# Power_Distribution_-_External_ADC.net
KiCad netlist of a schematic drawn in Altium Designer
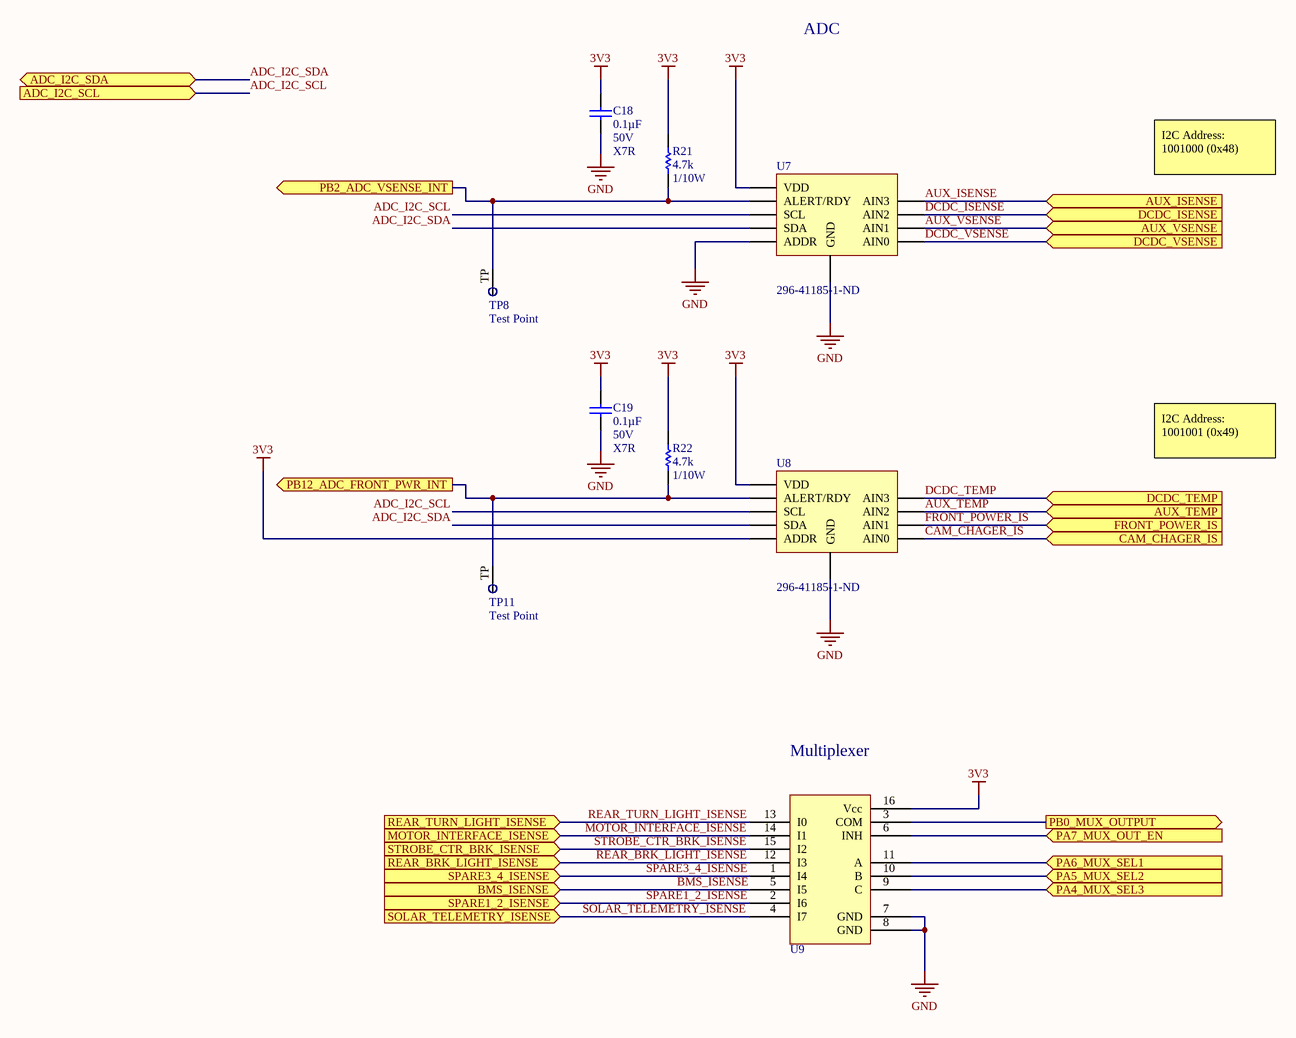
[diagram p0: Power Distribution - External ADC.SchDoc]

(export (version "E")
  (design (tool "Eeschema 10.0.6"))
  (components
    (comp (ref "C18")
      (value "CAP CER 0.1UF 50V 10% X7R 0603")
      (footprint "CAP, 0603")
      (description "0.10µF ±10% 50V Ceramic Capacitor X7R 0603 (1608 Metric)")
      (fields
        (field (name "TOLERANCE") "±10%")
        (field (name "CAPACITANCE") "0.1µF")
        (field (name "VOLTAGE") "50V")
        (field (name "TEMPERATURE COEFFICIENT") "X7R")
      )
      (libsource (lib "Schematic Diagrams") (part "CAP CER 0.1UF 50V 10% X7R 0603"))
    )
    (comp (ref "C19")
      (value "CAP CER 0.1UF 50V 10% X7R 0603")
      (footprint "CAP, 0603")
      (description "0.10µF ±10% 50V Ceramic Capacitor X7R 0603 (1608 Metric)")
      (fields
        (field (name "TOLERANCE") "±10%")
        (field (name "CAPACITANCE") "0.1µF")
        (field (name "VOLTAGE") "50V")
        (field (name "TEMPERATURE COEFFICIENT") "X7R")
      )
      (libsource (lib "Schematic Diagrams") (part "CAP CER 0.1UF 50V 10% X7R 0603"))
    )
    (comp (ref "R21")
      (value "RES 4.7K OHM 1% 1/10W 0603")
      (footprint "RES, 0603")
      (description "4.7k Ohm ±1% 0.1W, 1/10W Chip Resistor 0603 (1608 Metric) Moisture Resistant Thick Film")
      (fields
        (field (name "TOLERANCE") "±1%")
        (field (name "RESISTANCE (OHMS)") "4.7k")
        (field (name "POWER (WATTS)") "1/10W")
      )
      (libsource (lib "Schematic Diagrams") (part "RES 4.7K OHM 1% 1/10W 0603"))
    )
    (comp (ref "R22")
      (value "RES 4.7K OHM 1% 1/10W 0603")
      (footprint "RES, 0603")
      (description "4.7k Ohm ±1% 0.1W, 1/10W Chip Resistor 0603 (1608 Metric) Moisture Resistant Thick Film")
      (fields
        (field (name "TOLERANCE") "±1%")
        (field (name "RESISTANCE (OHMS)") "4.7k")
        (field (name "POWER (WATTS)") "1/10W")
      )
      (libsource (lib "Schematic Diagrams") (part "RES 4.7K OHM 1% 1/10W 0603"))
    )
    (comp (ref "TP8")
      (value "Test Point")
      (footprint "Test Point")
      (libsource (lib "Schematic Diagrams") (part "Test Point"))
    )
    (comp (ref "TP11")
      (value "Test Point")
      (footprint "Test Point")
      (libsource (lib "Schematic Diagrams") (part "Test Point"))
    )
    (comp (ref "U7")
      (value "Quad ADC")
      (footprint "IC ADC VSSOP10")
      (description "12 Bit Analog to Digital Converter 4 Input 1 Sigma-Delta 10-VSSOP")
      (fields
        (field (name "MANUFACTURER") "Texas Instruments")
        (field (name "MANUFACTURER PART NUMBER") "ADS1015IDGSR")
        (field (name "SUPPLIER PART NUMBER 1") "296-41185-1-ND")
      )
      (libsource (lib "Schematic Diagrams") (part "IC ADC 12-BIT VSSOP-10"))
    )
    (comp (ref "U8")
      (value "Quad ADC")
      (footprint "IC ADC VSSOP10")
      (description "12 Bit Analog to Digital Converter 4 Input 1 Sigma-Delta 10-VSSOP")
      (fields
        (field (name "MANUFACTURER") "Texas Instruments")
        (field (name "MANUFACTURER PART NUMBER") "ADS1015IDGSR")
        (field (name "SUPPLIER PART NUMBER 1") "296-41185-1-ND")
      )
      (libsource (lib "Schematic Diagrams") (part "IC ADC 12-BIT VSSOP-10"))
    )
    (comp (ref "U9")
      (value "IC MUX/DMUX 8X1 16TSSOP")
      (footprint "16-TSSOP")
      (description "1 Circuit IC Switch 8:1 75Ohm 16-TSSOP")
      (fields (field (name "MANUFACTURER") "Texas Instruments"))
      (libsource (lib "Schematic Diagrams") (part "IC MUX/DMUX 8X1 16TSSOP"))
    )
  )
  (nets
    (net (code "1") (name "/ADC_I2C_SCL") (class "Default")
      (node (ref "U7") (pin "10") (pinfunction "SCL_10") (pintype "passive"))
      (node (ref "U8") (pin "10") (pinfunction "SCL_10") (pintype "passive"))
    )
    (net (code "2") (name "/ADC_I2C_SDA") (class "Default")
      (node (ref "U7") (pin "9") (pinfunction "SDA_9") (pintype "passive"))
      (node (ref "U8") (pin "9") (pinfunction "SDA_9") (pintype "passive"))
    )
    (net (code "3") (name "/AUX_ISENSE") (class "Default")
      (node (ref "U7") (pin "7") (pinfunction "AIN3_7") (pintype "passive"))
    )
    (net (code "4") (name "/AUX_TEMP") (class "Default")
      (node (ref "U8") (pin "6") (pinfunction "AIN2_6") (pintype "passive"))
    )
    (net (code "5") (name "/AUX_VSENSE") (class "Default")
      (node (ref "U7") (pin "5") (pinfunction "AIN1_5") (pintype "passive"))
    )
    (net (code "6") (name "/BMS_ISENSE") (class "Default")
      (node (ref "U9") (pin "5") (pinfunction "I5_5") (pintype "passive"))
    )
    (net (code "7") (name "/CAM_CHAGER_IS") (class "Default")
      (node (ref "U8") (pin "4") (pinfunction "AIN0_4") (pintype "passive"))
    )
    (net (code "8") (name "/DCDC_ISENSE") (class "Default")
      (node (ref "U7") (pin "6") (pinfunction "AIN2_6") (pintype "passive"))
    )
    (net (code "9") (name "/DCDC_TEMP") (class "Default")
      (node (ref "U8") (pin "7") (pinfunction "AIN3_7") (pintype "passive"))
    )
    (net (code "10") (name "/DCDC_VSENSE") (class "Default")
      (node (ref "U7") (pin "4") (pinfunction "AIN0_4") (pintype "passive"))
    )
    (net (code "11") (name "/FRONT_POWER_IS") (class "Default")
      (node (ref "U8") (pin "5") (pinfunction "AIN1_5") (pintype "passive"))
    )
    (net (code "12") (name "/MOTOR_INTERFACE_ISENSE") (class "Default")
      (node (ref "U9") (pin "14") (pinfunction "I1_14") (pintype "passive"))
    )
    (net (code "13") (name "/PA4_MUX_SEL3") (class "Default")
      (node (ref "U9") (pin "9") (pinfunction "C_9") (pintype "passive"))
    )
    (net (code "14") (name "/PA5_MUX_SEL2") (class "Default")
      (node (ref "U9") (pin "10") (pinfunction "B_10") (pintype "passive"))
    )
    (net (code "15") (name "/PA6_MUX_SEL1") (class "Default")
      (node (ref "U9") (pin "11") (pinfunction "A_11") (pintype "passive"))
    )
    (net (code "16") (name "/PA7_MUX_OUT_EN") (class "Default")
      (node (ref "U9") (pin "6") (pinfunction "INH_6") (pintype "passive"))
    )
    (net (code "17") (name "/PB0_MUX_OUTPUT") (class "Default")
      (node (ref "U9") (pin "3") (pinfunction "COM_3") (pintype "passive"))
    )
    (net (code "18") (name "/PB2_ADC_VSENSE_INT") (class "Default")
      (node (ref "R21") (pin "2") (pinfunction "2_2") (pintype "passive"))
      (node (ref "TP8") (pin "TP") (pinfunction "1_TP") (pintype "passive"))
      (node (ref "U7") (pin "2") (pinfunction "ALERT/RDY_2") (pintype "passive"))
    )
    (net (code "19") (name "/PB12_ADC_FRONT_PWR_INT") (class "Default")
      (node (ref "R22") (pin "2") (pinfunction "2_2") (pintype "passive"))
      (node (ref "TP11") (pin "TP") (pinfunction "1_TP") (pintype "passive"))
      (node (ref "U8") (pin "2") (pinfunction "ALERT/RDY_2") (pintype "passive"))
    )
    (net (code "20") (name "/REAR_BRK_LIGHT_ISENSE") (class "Default")
      (node (ref "U9") (pin "12") (pinfunction "I3_12") (pintype "passive"))
    )
    (net (code "21") (name "/REAR_TURN_LIGHT_ISENSE") (class "Default")
      (node (ref "U9") (pin "13") (pinfunction "I0_13") (pintype "passive"))
    )
    (net (code "22") (name "/SOLAR_TELEMETRY_ISENSE") (class "Default")
      (node (ref "U9") (pin "4") (pinfunction "I7_4") (pintype "passive"))
    )
    (net (code "23") (name "/SPARE1_2_ISENSE") (class "Default")
      (node (ref "U9") (pin "2") (pinfunction "I6_2") (pintype "passive"))
    )
    (net (code "24") (name "/SPARE3_4_ISENSE") (class "Default")
      (node (ref "U9") (pin "1") (pinfunction "I4_1") (pintype "passive"))
    )
    (net (code "25") (name "/STROBE_CTR_BRK_ISENSE") (class "Default")
      (node (ref "U9") (pin "15") (pinfunction "I2_15") (pintype "passive"))
    )
    (net (code "26") (name "3V3") (class "Default")
      (node (ref "C18") (pin "1") (pinfunction "1_1") (pintype "passive"))
      (node (ref "C19") (pin "1") (pinfunction "1_1") (pintype "passive"))
      (node (ref "R21") (pin "1") (pinfunction "1_1") (pintype "passive"))
      (node (ref "R22") (pin "1") (pinfunction "1_1") (pintype "passive"))
      (node (ref "U7") (pin "8") (pinfunction "VDD_8") (pintype "passive"))
      (node (ref "U8") (pin "1") (pinfunction "ADDR_1") (pintype "passive"))
      (node (ref "U8") (pin "8") (pinfunction "VDD_8") (pintype "passive"))
      (node (ref "U9") (pin "16") (pinfunction "Vcc_16") (pintype "passive"))
    )
    (net (code "27") (name "GND") (class "Default")
      (node (ref "C18") (pin "2") (pinfunction "2_2") (pintype "passive"))
      (node (ref "C19") (pin "2") (pinfunction "2_2") (pintype "passive"))
      (node (ref "U7") (pin "1") (pinfunction "ADDR_1") (pintype "passive"))
      (node (ref "U7") (pin "3") (pinfunction "GND_3") (pintype "passive"))
      (node (ref "U8") (pin "3") (pinfunction "GND_3") (pintype "passive"))
      (node (ref "U9") (pin "7") (pinfunction "GND_7") (pintype "passive"))
      (node (ref "U9") (pin "8") (pinfunction "GND_8") (pintype "passive"))
    )
  )
)
